# MT3620AvnetModule.net
KiCad netlist of a schematic drawn in Altium Designer
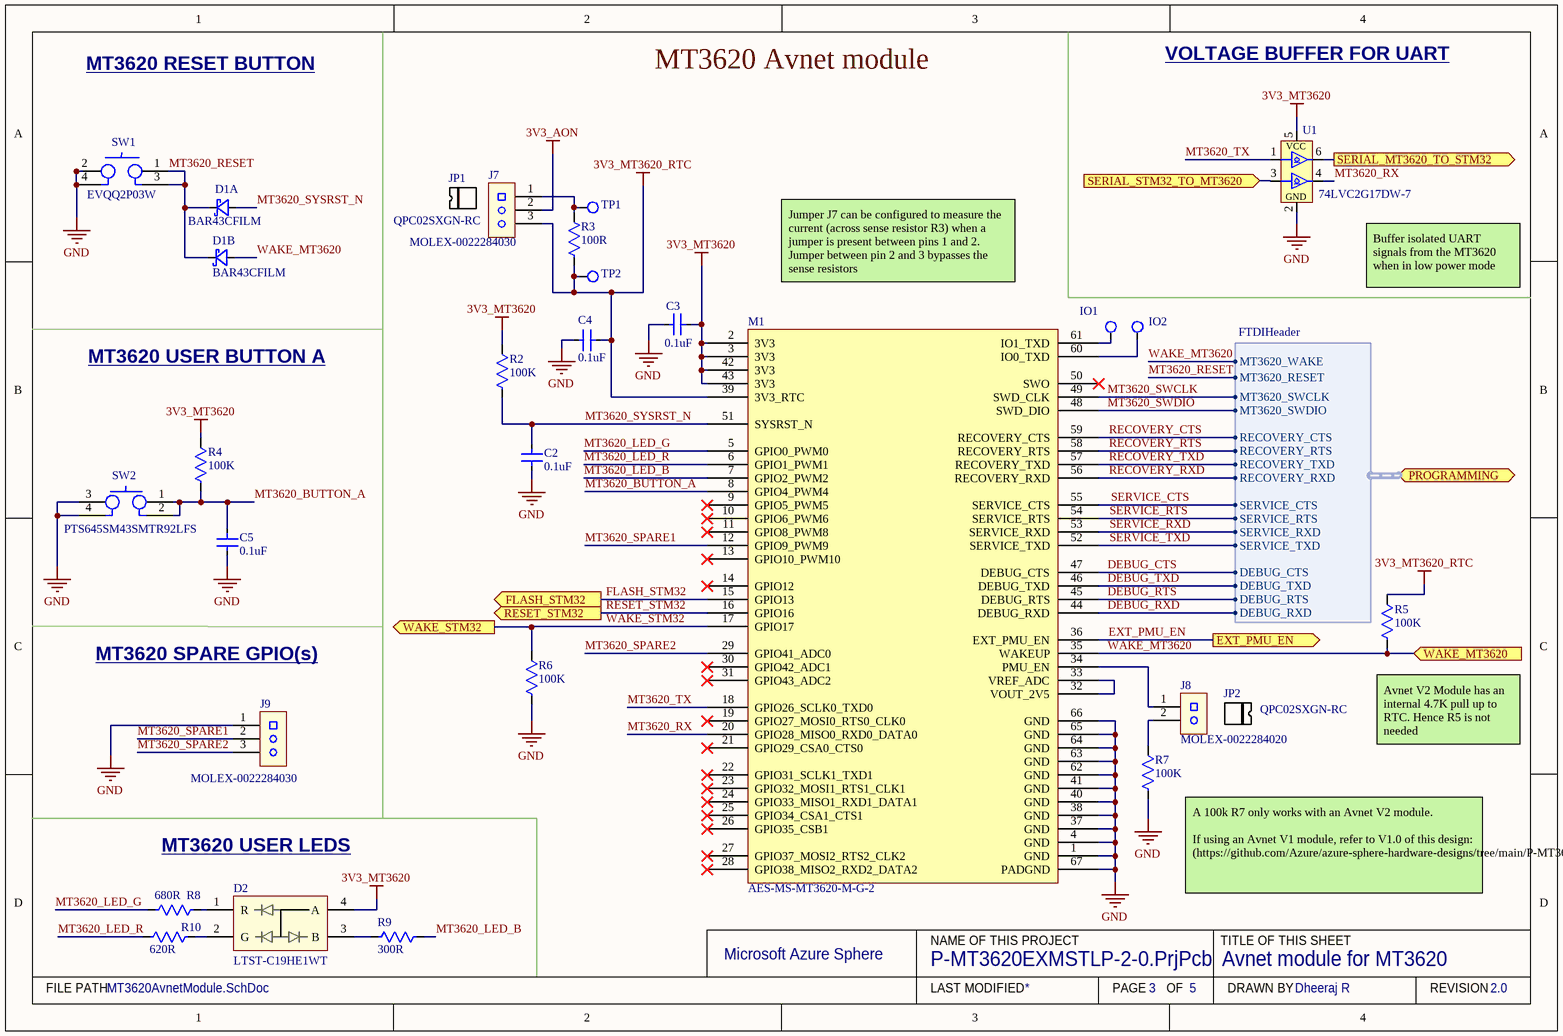
[diagram p0: MT3620AvnetModule.SchDoc]

(export (version "E")
  (design (tool "Eeschema 10.0.6"))
  (components
    (comp (ref "C2")
      (value "0.1uF")
      (footprint "CC0603")
      (description "0.1uF, 0603, CC0603KRX7R8BB104, Yageo, 25V, X7R, 10%, FULL REEL")
      (fields
        (field (name "MANUFACTURER") "Yageo")
        (field (name "MANUFACTURER PART NUMBER") "CC0603KRX7R8BB104")
      )
      (libsource (lib "Yageo") (part "CC0603KRX7R8BB104"))
    )
    (comp (ref "C3")
      (value "0.1uF")
      (footprint "CC0603")
      (description "0.1uF, 0603, CC0603KRX7R8BB104, Yageo, 25V, X7R, 10%, FULL REEL")
      (fields
        (field (name "MANUFACTURER") "Yageo")
        (field (name "MANUFACTURER PART NUMBER") "CC0603KRX7R8BB104")
      )
      (libsource (lib "Yageo") (part "CC0603KRX7R8BB104"))
    )
    (comp (ref "C4")
      (value "0.1uF")
      (footprint "CC0603")
      (description "0.1uF, 0603, CC0603KRX7R8BB104, Yageo, 25V, X7R, 10%, FULL REEL")
      (fields
        (field (name "MANUFACTURER") "Yageo")
        (field (name "MANUFACTURER PART NUMBER") "CC0603KRX7R8BB104")
      )
      (libsource (lib "Yageo") (part "CC0603KRX7R8BB104"))
    )
    (comp (ref "C5")
      (value "0.1uF")
      (footprint "CC0603")
      (description "0.1uF, 0603, CC0603KRX7R8BB104, Yageo, 25V, X7R, 10%, FULL REEL")
      (fields
        (field (name "MANUFACTURER") "Yageo")
        (field (name "MANUFACTURER PART NUMBER") "CC0603KRX7R8BB104")
      )
      (libsource (lib "Yageo") (part "CC0603KRX7R8BB104"))
    )
    (comp (ref "D1")
      (value "BAR43CFILM")
      (footprint "ON_SEMI-SOT23-3")
      (description "DIODE ARRAY SCHOTTKY 30V SOT23-3")
      (fields (field (name "MANUFACTURER") "STMicroelectronics"))
      (libsource (lib "ST") (part "BAR43CFILM"))
    )
    (comp (ref "D2")
      (value "LTST-C19HE1WT")
      (footprint "LTST-C19HE1WT")
      (description "LED RGB DIFFUSED 0606 SMD")
      (fields (field (name "MANUFACTURER") "Lite-On Inc."))
      (libsource (lib "Lite-On") (part "LTST-C19HE1WT"))
    )
    (comp (ref "IO1")
      (value "TestPoint")
      (footprint "Pad1.27mm")
      (description "Test Point")
      (libsource (lib "generic") (part "TestPoint"))
    )
    (comp (ref "IO2")
      (value "TestPoint")
      (footprint "Pad1.27mm")
      (description "Test Point")
      (libsource (lib "generic") (part "TestPoint"))
    )
    (comp (ref "J7")
      (value "MOLEX-0022284030")
      (footprint "0022284030")
      (description "CONN HEADER 3POS .100 VERT TIN")
      (fields
        (field (name "MANUFACTURER") "Molex, LLC")
        (field (name "MANUFACTURER PART NUMBER") "0022284030")
      )
      (libsource (lib "Molex") (part "MOLEX-0022284030"))
    )
    (comp (ref "J8")
      (value "MOLEX-0022284020")
      (footprint "0022284020")
      (description "CONN HEADER 2POS .100 VERT TIN")
      (fields
        (field (name "MANUFACTURER") "Molex, LLC")
        (field (name "MANUFACTURER PART NUMBER") "0022284020")
      )
      (libsource (lib "Molex") (part "MOLEX-0022284020"))
    )
    (comp (ref "J9")
      (value "MOLEX-0022284030")
      (footprint "0022284030")
      (description "CONN HEADER 3POS .100 VERT TIN")
      (fields
        (field (name "MANUFACTURER") "Molex, LLC")
        (field (name "MANUFACTURER PART NUMBER") "0022284030")
      )
      (libsource (lib "") (part "MOLEX-0022284030_1"))
    )
    (comp (ref "JP1")
      (value "QPC02SXGN-RC")
      (description "CONN JUMPER SHORTING .100\" GOLD")
      (fields (field (name "MANUFACTURER") "Sullins"))
      (libsource (lib "") (part "QPC02SXGN-RC_1"))
    )
    (comp (ref "JP2")
      (value "QPC02SXGN-RC")
      (description "CONN JUMPER SHORTING .100\" GOLD")
      (fields (field (name "MANUFACTURER") "Sullins"))
      (libsource (lib "SullinsConnectorSolutions") (part "QPC02SXGN-RC"))
    )
    (comp (ref "M1")
      (value "AES-MS-MT3620-M-G-2")
      (footprint "AES-MS-MT3620-M-G")
      (libsource (lib "Avnet") (part "AES-MS-MT3620-M-G (SAT)"))
    )
    (comp (ref "R2")
      (value "100K")
      (footprint "VISHAY-0603")
      (description "100K Ohm 0603 1% 0.1W(1/10W) 100ppm Paper T/R")
      (fields
        (field (name "MANUFACTURER") "Yageo")
        (field (name "MANUFACTURER PART NUMBER") "RC0603FR-07100KL")
      )
      (libsource (lib "Yageo") (part "RC0603FR-07100KL"))
    )
    (comp (ref "R3")
      (value "100R")
      (footprint "VISHAY-0603")
      (description "100 OHM Current Sense 0.1% 1/2W 0603")
      (fields
        (field (name "MANUFACTURER") "Vishay Dale Thin Film")
        (field (name "MANUFACTURER PART NUMBER") "PCAN0603E1000BST5")
      )
      (libsource (lib "Vishay") (part "PCAN0603E1000BST5"))
    )
    (comp (ref "R4")
      (value "100K")
      (footprint "VISHAY-0603")
      (description "100K Ohm 0603 1% 0.1W(1/10W) 100ppm Paper T/R")
      (fields
        (field (name "MANUFACTURER") "Yageo")
        (field (name "MANUFACTURER PART NUMBER") "RC0603FR-07100KL")
      )
      (libsource (lib "") (part "RC0603FR-07100KL_1"))
    )
    (comp (ref "R5")
      (value "100K")
      (footprint "VISHAY-0603")
      (description "100K Ohm 0603 1% 0.1W(1/10W) 100ppm Paper T/R")
      (fields
        (field (name "MANUFACTURER") "Yageo")
        (field (name "MANUFACTURER PART NUMBER") "RC0603FR-07100KL")
      )
      (libsource (lib "") (part "RC0603FR-07100KL_1"))
    )
    (comp (ref "R6")
      (value "100K")
      (footprint "VISHAY-0603")
      (description "100K Ohm 0603 1% 0.1W(1/10W) 100ppm Paper T/R")
      (fields
        (field (name "MANUFACTURER") "Yageo")
        (field (name "MANUFACTURER PART NUMBER") "RC0603FR-07100KL")
      )
      (libsource (lib "") (part "RC0603FR-07100KL_1"))
    )
    (comp (ref "R7")
      (value "100K")
      (footprint "VISHAY-0603")
      (description "100K Ohm 0603 1% 0.1W(1/10W) 100ppm Paper T/R")
      (fields
        (field (name "MANUFACTURER") "Yageo")
        (field (name "MANUFACTURER PART NUMBER") "RC0603FR-07100KL")
      )
      (libsource (lib "Yageo") (part "RC0603FR-07100KL"))
    )
    (comp (ref "R8")
      (value "680R")
      (footprint "RC0603")
      (description "680R, 0603 YAGEO - RC0603FR-07680RL - SMD Chip Resistor, RC Series, 50 V, Thick Film, 100 mW")
      (fields
        (field (name "MANUFACTURER") "Yageo")
        (field (name "MANUFACTURER PART NUMBER") "RC0603FR-07680RL")
      )
      (libsource (lib "Yageo") (part "RC0603FR-07680RL"))
    )
    (comp (ref "R9")
      (value "300R")
      (footprint "RC0603")
      (description "300 Ohm, 0603, 1% 0.1W(1/10W) 100ppm/ C Molded SMD Paper T/R")
      (fields
        (field (name "MANUFACTURER") "Yageo")
        (field (name "MANUFACTURER PART NUMBER") "RC0603FR-07300RL")
      )
      (libsource (lib "Yageo") (part "RC0603FR-07300RL"))
    )
    (comp (ref "R10")
      (value "620R")
      (footprint "RC0603")
      (description "620 Ohm, 0603, 1% 0.1W(1/10W) 100ppm/ C Molded SMD Paper T/R")
      (fields
        (field (name "MANUFACTURER") "Yageo")
        (field (name "MANUFACTURER PART NUMBER") "RC0603FR-07620RL")
      )
      (libsource (lib "Yageo") (part "RC0603FR-07620RL"))
    )
    (comp (ref "SW1")
      (value "SWI TACT SPN0 PANASONIC EVQQ2P03W")
      (footprint "EVQQ2P03W")
      (description "PANASONIC - EVQQ2P03W - SWITCH, SPNO, SMD")
      (fields (field (name "MANUFACTURER") "PANASONIC") (field (name "MANUFACTURER PART NUMBER") "EVQQ2P03W"))
      (libsource (lib "switch") (part "SWI TACT SPN0 PANASONIC EVQQ2P03W"))
    )
    (comp (ref "SW2")
      (value "PTS645SM43SMTR92LFS")
      (footprint "C&K PTS645SM43SMTR92LFS")
      (description "SWITCH TACTILE SPST-NO 0.05A 12V")
      (fields (field (name "MANUFACTURER") "ITT C&K"))
      (libsource (lib "C&K") (part "PTS645SM43SMTR92LFS"))
    )
    (comp (ref "TP1")
      (value "TestPointHole")
      (footprint "PTH1.27mm-0.9mm")
      (description "Test Point With Hole")
      (libsource (lib "generic") (part "TestPointHole"))
    )
    (comp (ref "TP2")
      (value "TestPointHole")
      (footprint "PTH1.27mm-0.9mm")
      (description "Test Point With Hole")
      (libsource (lib "generic") (part "TestPointHole"))
    )
    (comp (ref "U1")
      (value "74LVC2G17DW-7")
      (footprint "Nexperia-SOT363")
      (description "Buffers & Line Drivers LVC 2 Gates LOGIC")
      (fields (field (name "MANUFACTURER") "Diodes"))
      (libsource (lib "DiodesInc") (part "74LVC2G17DW-7"))
    )
  )
  (nets
    (net (code "2") (name "/DEBUG_CTS") (class "Default")
      (node (ref "M1") (pin "47") (pinfunction "DEBUG_CTS_47") (pintype "passive"))
    )
    (net (code "3") (name "/DEBUG_RTS") (class "Default")
      (node (ref "M1") (pin "45") (pinfunction "DEBUG_RTS_45") (pintype "passive"))
    )
    (net (code "4") (name "/DEBUG_RXD") (class "Default")
      (node (ref "M1") (pin "44") (pinfunction "DEBUG_RXD_44") (pintype "passive"))
    )
    (net (code "5") (name "/DEBUG_TXD") (class "Default")
      (node (ref "M1") (pin "46") (pinfunction "DEBUG_TXD_46") (pintype "passive"))
    )
    (net (code "6") (name "/EXT_PMU_EN") (class "Default")
      (node (ref "M1") (pin "36") (pinfunction "EXT_PMU_EN_36") (pintype "passive"))
    )
    (net (code "7") (name "/FLASH_STM32") (class "Default")
      (node (ref "M1") (pin "15") (pinfunction "GPIO13_15") (pintype "passive"))
    )
    (net (code "8") (name "/MT3620_BUTTON_A") (class "Default")
      (node (ref "C5") (pin "2") (pinfunction "2_2") (pintype "passive"))
      (node (ref "M1") (pin "8") (pinfunction "GPIO4_PWM4_8") (pintype "passive"))
      (node (ref "R4") (pin "1") (pinfunction "1_1") (pintype "passive"))
      (node (ref "SW2") (pin "1") (pinfunction "1_1") (pintype "passive"))
      (node (ref "SW2") (pin "2") (pinfunction "2_2") (pintype "passive"))
    )
    (net (code "9") (name "/MT3620_LED_B") (class "Default")
      (node (ref "M1") (pin "7") (pinfunction "GPIO2_PWM2_7") (pintype "passive"))
      (node (ref "R9") (pin "2") (pinfunction "2_2") (pintype "passive"))
    )
    (net (code "10") (name "/MT3620_LED_G") (class "Default")
      (node (ref "M1") (pin "5") (pinfunction "GPIO0_PWM0_5") (pintype "passive"))
      (node (ref "R8") (pin "1") (pinfunction "1_1") (pintype "passive"))
    )
    (net (code "11") (name "/MT3620_LED_R") (class "Default")
      (node (ref "M1") (pin "6") (pinfunction "GPIO1_PWM1_6") (pintype "passive"))
      (node (ref "R10") (pin "1") (pinfunction "1_1") (pintype "passive"))
    )
    (net (code "12") (name "/MT3620_RESET") (class "Default")
      (node (ref "D1") (pin "3") (pinfunction "K_3") (pintype "passive"))
      (node (ref "SW1") (pin "1") (pinfunction "1_1") (pintype "passive"))
      (node (ref "SW1") (pin "3") (pinfunction "3_3") (pintype "passive"))
    )
    (net (code "13") (name "/MT3620_RX") (class "Default")
      (node (ref "M1") (pin "20") (pinfunction "GPIO28_MISO0_RXD0_DATA0_20") (pintype "passive"))
      (node (ref "U1") (pin "4") (pinfunction "4_4") (pintype "passive"))
    )
    (net (code "14") (name "/MT3620_SPARE1") (class "Default")
      (node (ref "J9") (pin "2") (pinfunction "2_2") (pintype "passive"))
      (node (ref "M1") (pin "12") (pinfunction "GPIO9_PWM9_12") (pintype "passive"))
    )
    (net (code "15") (name "/MT3620_SPARE2") (class "Default")
      (node (ref "J9") (pin "3") (pinfunction "3_3") (pintype "passive"))
      (node (ref "M1") (pin "29") (pinfunction "GPIO41_ADC0_29") (pintype "passive"))
    )
    (net (code "16") (name "/MT3620_SWCLK") (class "Default")
      (node (ref "M1") (pin "49") (pinfunction "SWD_CLK_49") (pintype "passive"))
    )
    (net (code "17") (name "/MT3620_SWDIO") (class "Default")
      (node (ref "M1") (pin "48") (pinfunction "SWD_DIO_48") (pintype "passive"))
    )
    (net (code "18") (name "/MT3620_SYSRST_N") (class "Default")
      (node (ref "C2") (pin "2") (pinfunction "2_2") (pintype "passive"))
      (node (ref "D1") (pin "1") (pinfunction "A1_1") (pintype "passive"))
      (node (ref "M1") (pin "51") (pinfunction "SYSRST_N_51") (pintype "passive"))
      (node (ref "R2") (pin "1") (pinfunction "1_1") (pintype "passive"))
    )
    (net (code "19") (name "/MT3620_TX") (class "Default")
      (node (ref "M1") (pin "18") (pinfunction "GPIO26_SCLK0_TXD0_18") (pintype "passive"))
      (node (ref "U1") (pin "1") (pinfunction "1_1") (pintype "passive"))
    )
    (net (code "20") (name "/RECOVERY_CTS") (class "Default")
      (node (ref "M1") (pin "59") (pinfunction "RECOVERY_CTS_59") (pintype "passive"))
    )
    (net (code "21") (name "/RECOVERY_RTS") (class "Default")
      (node (ref "M1") (pin "58") (pinfunction "RECOVERY_RTS_58") (pintype "passive"))
    )
    (net (code "22") (name "/RECOVERY_RXD") (class "Default")
      (node (ref "M1") (pin "56") (pinfunction "RECOVERY_RXD_56") (pintype "passive"))
    )
    (net (code "23") (name "/RECOVERY_TXD") (class "Default")
      (node (ref "M1") (pin "57") (pinfunction "RECOVERY_TXD_57") (pintype "passive"))
    )
    (net (code "24") (name "/RESET_STM32") (class "Default")
      (node (ref "M1") (pin "16") (pinfunction "GPIO16_16") (pintype "passive"))
    )
    (net (code "25") (name "/SERIAL_MT3620_TO_STM32") (class "Default")
      (node (ref "U1") (pin "6") (pinfunction "6_6") (pintype "passive"))
    )
    (net (code "26") (name "/SERIAL_STM32_TO_MT3620") (class "Default")
      (node (ref "U1") (pin "3") (pinfunction "3_3") (pintype "passive"))
    )
    (net (code "27") (name "/SERVICE_CTS") (class "Default")
      (node (ref "M1") (pin "55") (pinfunction "SERVICE_CTS_55") (pintype "passive"))
    )
    (net (code "28") (name "/SERVICE_RTS") (class "Default")
      (node (ref "M1") (pin "54") (pinfunction "SERVICE_RTS_54") (pintype "passive"))
    )
    (net (code "29") (name "/SERVICE_RXD") (class "Default")
      (node (ref "M1") (pin "53") (pinfunction "SERVICE_RXD_53") (pintype "passive"))
    )
    (net (code "30") (name "/SERVICE_TXD") (class "Default")
      (node (ref "M1") (pin "52") (pinfunction "SERVICE_TXD_52") (pintype "passive"))
    )
    (net (code "31") (name "/WAKE_MT3620") (class "Default")
      (node (ref "D1") (pin "2") (pinfunction "A2_2") (pintype "passive"))
      (node (ref "M1") (pin "35") (pinfunction "WAKEUP_35") (pintype "passive"))
      (node (ref "R5") (pin "1") (pinfunction "1_1") (pintype "passive"))
    )
    (net (code "32") (name "/WAKE_STM32") (class "Default")
      (node (ref "M1") (pin "17") (pinfunction "GPIO17_17") (pintype "passive"))
      (node (ref "R6") (pin "2") (pinfunction "2_2") (pintype "passive"))
    )
    (net (code "34") (name "3V3_AON") (class "Default")
      (node (ref "J7") (pin "2") (pinfunction "2_2") (pintype "passive"))
    )
    (net (code "35") (name "3V3_MT3620") (class "Default")
      (node (ref "C3") (pin "2") (pinfunction "2_2") (pintype "passive"))
      (node (ref "D2") (pin "4") (pinfunction "A_4") (pintype "passive"))
      (node (ref "M1") (pin "2") (pinfunction "3V3_2") (pintype "passive"))
      (node (ref "M1") (pin "3") (pinfunction "3V3_3") (pintype "passive"))
      (node (ref "M1") (pin "42") (pinfunction "3V3_42") (pintype "passive"))
      (node (ref "M1") (pin "43") (pinfunction "3V3_43") (pintype "passive"))
      (node (ref "R2") (pin "2") (pinfunction "2_2") (pintype "passive"))
      (node (ref "R4") (pin "2") (pinfunction "2_2") (pintype "passive"))
      (node (ref "U1") (pin "5") (pinfunction "5_5") (pintype "passive"))
    )
    (net (code "36") (name "3V3_MT3620_RTC") (class "Default")
      (node (ref "C4") (pin "2") (pinfunction "2_2") (pintype "passive"))
      (node (ref "J7") (pin "3") (pinfunction "3_3") (pintype "passive"))
      (node (ref "M1") (pin "39") (pinfunction "3V3_RTC_39") (pintype "passive"))
      (node (ref "R3") (pin "2") (pinfunction "2_2") (pintype "passive"))
      (node (ref "R5") (pin "2") (pinfunction "2_2") (pintype "passive"))
      (node (ref "TP2") (pin "1") (pinfunction "1_1") (pintype "passive"))
    )
    (net (code "37") (name "GND") (class "Default")
      (node (ref "C2") (pin "1") (pinfunction "1_1") (pintype "passive"))
      (node (ref "C3") (pin "1") (pinfunction "1_1") (pintype "passive"))
      (node (ref "C4") (pin "1") (pinfunction "1_1") (pintype "passive"))
      (node (ref "C5") (pin "1") (pinfunction "1_1") (pintype "passive"))
      (node (ref "J9") (pin "1") (pinfunction "1_1") (pintype "passive"))
      (node (ref "M1") (pin "1") (pinfunction "GND_1") (pintype "passive"))
      (node (ref "M1") (pin "37") (pinfunction "GND_37") (pintype "passive"))
      (node (ref "M1") (pin "38") (pinfunction "GND_38") (pintype "passive"))
      (node (ref "M1") (pin "4") (pinfunction "GND_4") (pintype "passive"))
      (node (ref "M1") (pin "40") (pinfunction "GND_40") (pintype "passive"))
      (node (ref "M1") (pin "41") (pinfunction "GND_41") (pintype "passive"))
      (node (ref "M1") (pin "62") (pinfunction "GND_62") (pintype "passive"))
      (node (ref "M1") (pin "63") (pinfunction "GND_63") (pintype "passive"))
      (node (ref "M1") (pin "64") (pinfunction "GND_64") (pintype "passive"))
      (node (ref "M1") (pin "65") (pinfunction "GND_65") (pintype "passive"))
      (node (ref "M1") (pin "66") (pinfunction "GND_66") (pintype "passive"))
      (node (ref "M1") (pin "67") (pinfunction "PADGND_67") (pintype "passive"))
      (node (ref "R6") (pin "1") (pinfunction "1_1") (pintype "passive"))
      (node (ref "R7") (pin "1") (pinfunction "1_1") (pintype "passive"))
      (node (ref "SW1") (pin "2") (pinfunction "2_2") (pintype "passive"))
      (node (ref "SW1") (pin "4") (pinfunction "4_4") (pintype "passive"))
      (node (ref "SW2") (pin "3") (pinfunction "3_3") (pintype "passive"))
      (node (ref "SW2") (pin "4") (pinfunction "4_4") (pintype "passive"))
      (node (ref "U1") (pin "2") (pinfunction "2_2") (pintype "passive"))
    )
    (net (code "38") (name "Net-(D2-B)") (class "Default")
      (node (ref "D2") (pin "3") (pinfunction "B_3") (pintype "passive"))
      (node (ref "R9") (pin "1") (pinfunction "1_1") (pintype "passive"))
    )
    (net (code "39") (name "Net-(D2-G)") (class "Default")
      (node (ref "D2") (pin "2") (pinfunction "G_2") (pintype "passive"))
      (node (ref "R10") (pin "2") (pinfunction "2_2") (pintype "passive"))
    )
    (net (code "40") (name "Net-(D2-R)") (class "Default")
      (node (ref "D2") (pin "1") (pinfunction "R_1") (pintype "passive"))
      (node (ref "R8") (pin "2") (pinfunction "2_2") (pintype "passive"))
    )
    (net (code "41") (name "Net-(J7-Pad1)") (class "Default")
      (node (ref "J7") (pin "1") (pinfunction "1_1") (pintype "passive"))
      (node (ref "R3") (pin "1") (pinfunction "1_1") (pintype "passive"))
      (node (ref "TP1") (pin "1") (pinfunction "1_1") (pintype "passive"))
    )
    (net (code "42") (name "Net-(J8-Pad2)") (class "Default")
      (node (ref "J8") (pin "2") (pinfunction "2_2") (pintype "passive"))
      (node (ref "R7") (pin "2") (pinfunction "2_2") (pintype "passive"))
    )
    (net (code "43") (name "Net-(M1-IO0_TXD)") (class "Default")
      (node (ref "IO2") (pin "1") (pinfunction "1_1") (pintype "passive"))
      (node (ref "M1") (pin "60") (pinfunction "IO0_TXD_60") (pintype "passive"))
    )
    (net (code "44") (name "Net-(M1-IO1_TXD)") (class "Default")
      (node (ref "IO1") (pin "1") (pinfunction "1_1") (pintype "passive"))
      (node (ref "M1") (pin "61") (pinfunction "IO1_TXD_61") (pintype "passive"))
    )
    (net (code "45") (name "Net-(M1-PMU_EN)") (class "Default")
      (node (ref "J8") (pin "1") (pinfunction "1_1") (pintype "passive"))
      (node (ref "M1") (pin "34") (pinfunction "PMU_EN_34") (pintype "passive"))
    )
    (net (code "46") (name "Net-(M1-VOUT_2V5)") (class "Default")
      (node (ref "M1") (pin "32") (pinfunction "VOUT_2V5_32") (pintype "passive"))
      (node (ref "M1") (pin "33") (pinfunction "VREF_ADC_33") (pintype "passive"))
    )
    (net (code "47") (name "unconnected-(M1-GPIO5_PWM5-Pad9)") (class "Default")
      (node (ref "M1") (pin "9") (pinfunction "GPIO5_PWM5_9") (pintype "passive+no_connect"))
    )
    (net (code "48") (name "unconnected-(M1-GPIO6_PWM6-Pad10)") (class "Default")
      (node (ref "M1") (pin "10") (pinfunction "GPIO6_PWM6_10") (pintype "passive+no_connect"))
    )
    (net (code "49") (name "unconnected-(M1-GPIO8_PWM8-Pad11)") (class "Default")
      (node (ref "M1") (pin "11") (pinfunction "GPIO8_PWM8_11") (pintype "passive+no_connect"))
    )
    (net (code "50") (name "unconnected-(M1-GPIO10_PWM10-Pad13)") (class "Default")
      (node (ref "M1") (pin "13") (pinfunction "GPIO10_PWM10_13") (pintype "passive+no_connect"))
    )
    (net (code "51") (name "unconnected-(M1-GPIO12-Pad14)") (class "Default")
      (node (ref "M1") (pin "14") (pinfunction "GPIO12_14") (pintype "passive+no_connect"))
    )
    (net (code "52") (name "unconnected-(M1-GPIO27_MOSI0_RTS0_CLK0-Pad19)") (class "Default")
      (node (ref "M1") (pin "19") (pinfunction "GPIO27_MOSI0_RTS0_CLK0_19") (pintype "passive+no_connect"))
    )
    (net (code "53") (name "unconnected-(M1-GPIO29_CSA0_CTS0-Pad21)") (class "Default")
      (node (ref "M1") (pin "21") (pinfunction "GPIO29_CSA0_CTS0_21") (pintype "passive+no_connect"))
    )
    (net (code "54") (name "unconnected-(M1-GPIO31_SCLK1_TXD1-Pad22)") (class "Default")
      (node (ref "M1") (pin "22") (pinfunction "GPIO31_SCLK1_TXD1_22") (pintype "passive+no_connect"))
    )
    (net (code "55") (name "unconnected-(M1-GPIO32_MOSI1_RTS1_CLK1-Pad23)") (class "Default")
      (node (ref "M1") (pin "23") (pinfunction "GPIO32_MOSI1_RTS1_CLK1_23") (pintype "passive+no_connect"))
    )
    (net (code "56") (name "unconnected-(M1-GPIO33_MISO1_RXD1_DATA1-Pad24)") (class "Default")
      (node (ref "M1") (pin "24") (pinfunction "GPIO33_MISO1_RXD1_DATA1_24") (pintype "passive+no_connect"))
    )
    (net (code "57") (name "unconnected-(M1-GPIO34_CSA1_CTS1-Pad25)") (class "Default")
      (node (ref "M1") (pin "25") (pinfunction "GPIO34_CSA1_CTS1_25") (pintype "passive+no_connect"))
    )
    (net (code "58") (name "unconnected-(M1-GPIO35_CSB1-Pad26)") (class "Default")
      (node (ref "M1") (pin "26") (pinfunction "GPIO35_CSB1_26") (pintype "passive+no_connect"))
    )
    (net (code "59") (name "unconnected-(M1-GPIO37_MOSI2_RTS2_CLK2-Pad27)") (class "Default")
      (node (ref "M1") (pin "27") (pinfunction "GPIO37_MOSI2_RTS2_CLK2_27") (pintype "passive+no_connect"))
    )
    (net (code "60") (name "unconnected-(M1-GPIO38_MISO2_RXD2_DATA2-Pad28)") (class "Default")
      (node (ref "M1") (pin "28") (pinfunction "GPIO38_MISO2_RXD2_DATA2_28") (pintype "passive+no_connect"))
    )
    (net (code "61") (name "unconnected-(M1-GPIO42_ADC1-Pad30)") (class "Default")
      (node (ref "M1") (pin "30") (pinfunction "GPIO42_ADC1_30") (pintype "passive+no_connect"))
    )
    (net (code "62") (name "unconnected-(M1-GPIO43_ADC2-Pad31)") (class "Default")
      (node (ref "M1") (pin "31") (pinfunction "GPIO43_ADC2_31") (pintype "passive+no_connect"))
    )
    (net (code "63") (name "unconnected-(M1-SWO-Pad50)") (class "Default")
      (node (ref "M1") (pin "50") (pinfunction "SWO_50") (pintype "passive+no_connect"))
    )
  )
)
